# MeasOutUI.net
KiCad netlist of a schematic drawn in Altium Designer
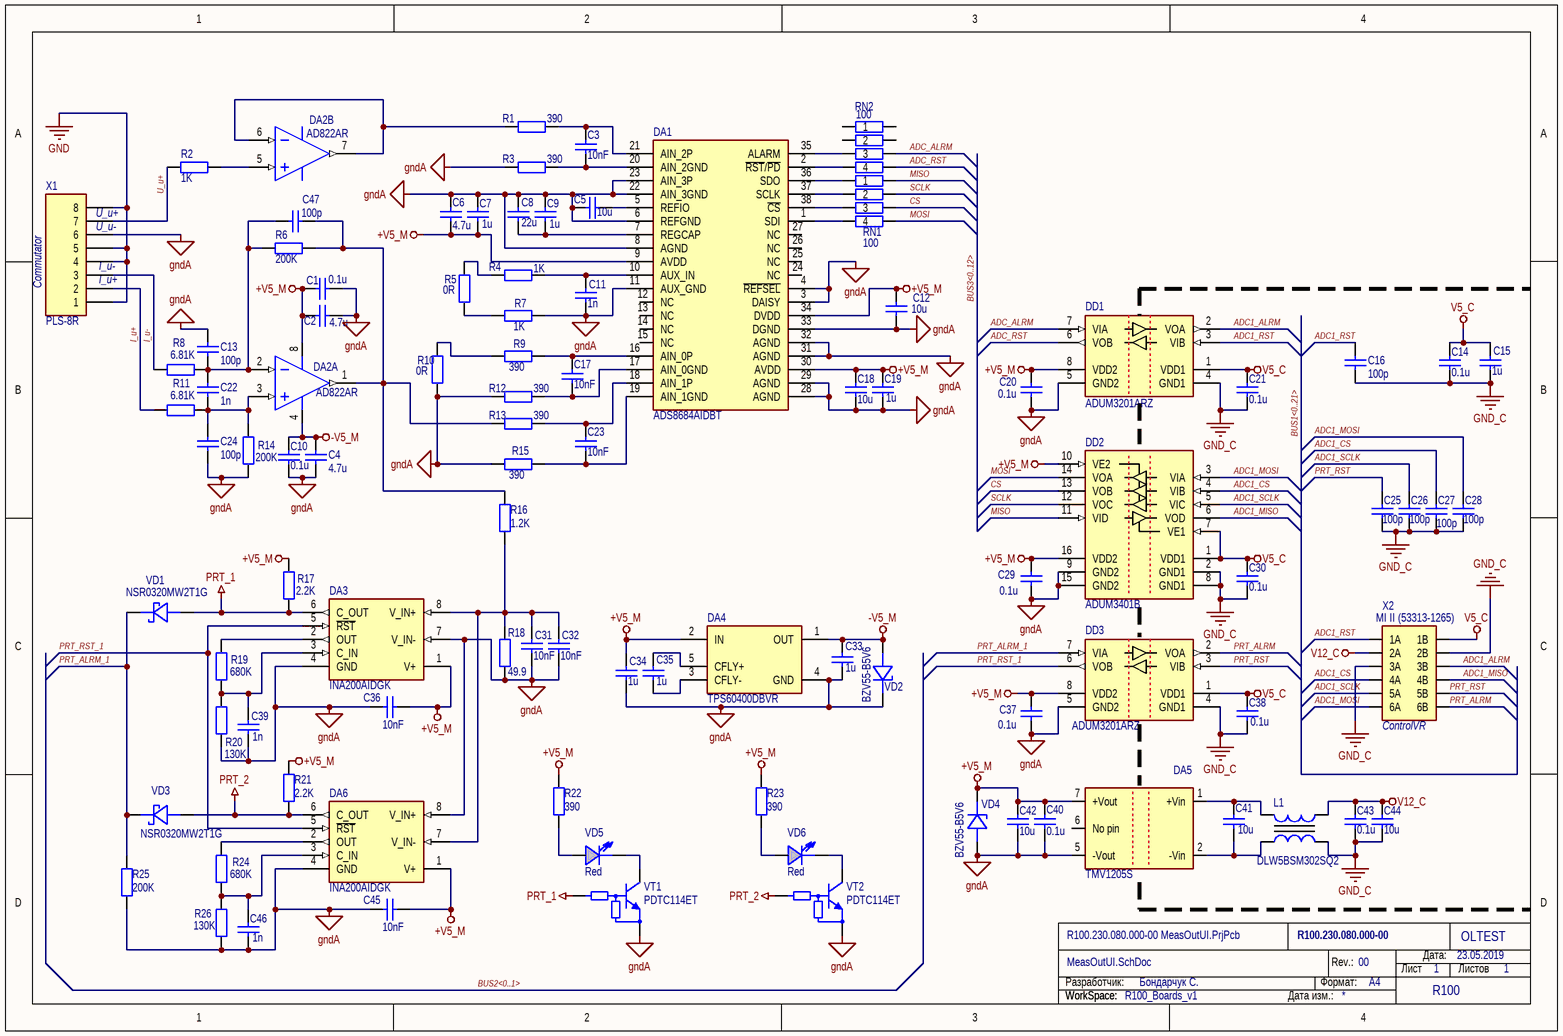
[diagram p0: MeasOutUI.SchDoc]

(export (version "E")
  (design (tool "Eeschema 10.0.6"))
  (components
    (comp (ref "C1")
      (value "0.1u")
      (footprint "mainLib:SMD_C_0603")
      (description "SMD C 0603 MURATA 50V 10% X7R")
      (fields (field (name "PARTNUMBER") "GRM188R71H104K") (field (name "MANUFACTURER") "MURATA"))
      (libsource (lib "mainRCLib") (part "C0603 0.1u 50V 10%"))
    )
    (comp (ref "C2")
      (value "4.7u")
      (footprint "mainLib:SMD_C_0805")
      (description "SMD C 0805 MURATA 50V 5% NP0")
      (fields (field (name "PARTNUMBER") "GRM21BR61E475M") (field (name "MANUFACTURER") "MURATA"))
      (libsource (lib "mainRCLib") (part "C0805 4.7u 25V 20%  X5R"))
    )
    (comp (ref "C3")
      (value "10nF")
      (footprint "mainLib:SMD_C_0603")
      (description "SMD C 0603 MURATA 100V 10% X7R")
      (fields (field (name "PARTNUMBER") "GRJ188R72A103KE11#") (field (name "MANUFACTURER") "MURATA"))
      (libsource (lib "mainRCLib") (part "C0603 10nF 100V 10%"))
    )
    (comp (ref "C4")
      (value "4.7u")
      (footprint "mainLib:SMD_C_0805")
      (description "SMD C 0805 MURATA 50V 5% NP0")
      (fields (field (name "PARTNUMBER") "GRM21BR61E475M") (field (name "MANUFACTURER") "MURATA"))
      (libsource (lib "mainRCLib") (part "C0805 4.7u 25V 20%  X5R"))
    )
    (comp (ref "C5")
      (value "10u")
      (footprint "mainLib:SMD_C_1206")
      (description "SMD C 1206 MURATA 25V 20% X5R")
      (fields (field (name "PARTNUMBER") "GRM31MR61E106M") (field (name "MANUFACTURER") "MURATA"))
      (libsource (lib "mainRCLib") (part "C1206 10u 25V 20%"))
    )
    (comp (ref "C6")
      (value "4.7u")
      (footprint "mainLib:SMD_C_0805")
      (description "SMD C 0805 MURATA 50V 5% NP0")
      (fields (field (name "PARTNUMBER") "GRM21BR61E475M") (field (name "MANUFACTURER") "MURATA"))
      (libsource (lib "mainRCLib") (part "C0805 4.7u 25V 20%  X5R"))
    )
    (comp (ref "C7")
      (value "1u")
      (footprint "mainLib:SMD_C_0603")
      (description "SMD C 0603 MURATA 25V 10% X7R")
      (fields (field (name "PARTNUMBER") "GRM188R71E105KA12") (field (name "MANUFACTURER") "MURATA"))
      (libsource (lib "mainRCLib") (part "C0603 1uF 25V 10%"))
    )
    (comp (ref "C8")
      (value "22u")
      (footprint "mainLib:SMD_C_1210")
      (description "SMD C 1210 MURATA 22uF 25V 10%  X7R")
      (fields (field (name "PARTNUMBER") "GRM32ER71E226K") (field (name "MANUFACTURER") "MURATA"))
      (libsource (lib "mainRCLib") (part "C1210 22u 25V 10%"))
    )
    (comp (ref "C9")
      (value "1u")
      (footprint "mainLib:SMD_C_0603")
      (description "SMD C 0603 MURATA 25V 10% X7R")
      (fields (field (name "PARTNUMBER") "GRM188R71E105KA12") (field (name "MANUFACTURER") "MURATA"))
      (libsource (lib "mainRCLib") (part "C0603 1uF 25V 10%"))
    )
    (comp (ref "C10")
      (value "0.1u")
      (footprint "mainLib:SMD_C_0603")
      (description "SMD C 0603 MURATA 50V 10% X7R")
      (fields (field (name "PARTNUMBER") "GRM188R71H104K") (field (name "MANUFACTURER") "MURATA"))
      (libsource (lib "mainRCLib") (part "C0603 0.1u 50V 10%"))
    )
    (comp (ref "C11")
      (value "1n")
      (footprint "mainLib:SMD_C_0603")
      (description "SMD C 0603 MURATA 50V 5% NP0")
      (fields (field (name "PARTNUMBER") "GRM1885C1H102JA01") (field (name "MANUFACTURER") "MURATA"))
      (libsource (lib "mainRCLib") (part "C0603 1n 50V 5%"))
    )
    (comp (ref "C12")
      (value "10u")
      (footprint "mainLib:SMD_C_1206")
      (description "SMD C 1206 MURATA 25V 20% X5R")
      (fields (field (name "PARTNUMBER") "GRM31MR61E106M") (field (name "MANUFACTURER") "MURATA"))
      (libsource (lib "mainRCLib") (part "C1206 10u 25V 20%"))
    )
    (comp (ref "C13")
      (value "100p")
      (footprint "mainLib:SMD_C_0603")
      (description "SMD C 0603 MURATA 100V 5% NP0")
      (fields (field (name "PARTNUMBER") "GRM1885C2A101JA01") (field (name "MANUFACTURER") "MURATA"))
      (libsource (lib "mainRCLib") (part "C0603 100p 100V 5%"))
    )
    (comp (ref "C14")
      (value "0.1u")
      (footprint "mainLib:SMD_C_0603")
      (description "SMD C 0603 MURATA 50V 10% X7R")
      (fields (field (name "PARTNUMBER") "GRM188R71H104K") (field (name "MANUFACTURER") "MURATA"))
      (libsource (lib "mainRCLib") (part "C0603 0.1u 50V 10%"))
    )
    (comp (ref "C15")
      (value "1u")
      (footprint "mainLib:SMD_C_0603")
      (description "SMD C 0603 MURATA 25V 10% X7R")
      (fields (field (name "PARTNUMBER") "GRM188R71E105KA12") (field (name "MANUFACTURER") "MURATA"))
      (libsource (lib "mainRCLib") (part "C0603 1uF 25V 10%"))
    )
    (comp (ref "C16")
      (value "100p")
      (footprint "mainLib:SMD_C_0603")
      (description "SMD C 0603 MURATA 100V 5% NP0")
      (fields (field (name "PARTNUMBER") "GRM1885C2A101JA01") (field (name "MANUFACTURER") "MURATA"))
      (libsource (lib "mainRCLib") (part "C0603 100p 100V 5%"))
    )
    (comp (ref "C17")
      (value "10nF")
      (footprint "mainLib:SMD_C_0603")
      (description "SMD C 0603 MURATA 100V 10% X7R")
      (fields (field (name "PARTNUMBER") "GRJ188R72A103KE11#") (field (name "MANUFACTURER") "MURATA"))
      (libsource (lib "mainRCLib") (part "C0603 10nF 100V 10%"))
    )
    (comp (ref "C18")
      (value "10u")
      (footprint "mainLib:SMD_C_1206")
      (description "SMD C 1206 MURATA 25V 20% X5R")
      (fields (field (name "PARTNUMBER") "GRM31MR61E106M") (field (name "MANUFACTURER") "MURATA"))
      (libsource (lib "mainRCLib") (part "C1206 10u 25V 20%"))
    )
    (comp (ref "C19")
      (value "1u")
      (footprint "mainLib:SMD_C_0603")
      (description "SMD C 0603 MURATA 25V 10% X7R")
      (fields (field (name "PARTNUMBER") "GRM188R71E105KA12") (field (name "MANUFACTURER") "MURATA"))
      (libsource (lib "mainRCLib") (part "C0603 1uF 25V 10%"))
    )
    (comp (ref "C20")
      (value "0.1u")
      (footprint "mainLib:SMD_C_0603")
      (description "SMD C 0603 MURATA 50V 10% X7R")
      (fields (field (name "PARTNUMBER") "GRM188R71H104K") (field (name "MANUFACTURER") "MURATA"))
      (libsource (lib "mainRCLib") (part "C0603 0.1u 50V 10%"))
    )
    (comp (ref "C21")
      (value "0.1u")
      (footprint "mainLib:SMD_C_0603")
      (description "SMD C 0603 MURATA 50V 10% X7R")
      (fields (field (name "PARTNUMBER") "GRM188R71H104K") (field (name "MANUFACTURER") "MURATA"))
      (libsource (lib "mainRCLib") (part "C0603 0.1u 50V 10%"))
    )
    (comp (ref "C22")
      (value "1n")
      (footprint "mainLib:SMD_C_0603")
      (description "SMD C 0603 MURATA 50V 5% NP0")
      (fields (field (name "PARTNUMBER") "GRM1885C1H102JA01") (field (name "MANUFACTURER") "MURATA"))
      (libsource (lib "mainRCLib") (part "C0603 1n 50V 5%"))
    )
    (comp (ref "C23")
      (value "10nF")
      (footprint "mainLib:SMD_C_0603")
      (description "SMD C 0603 MURATA 100V 10% X7R")
      (fields (field (name "PARTNUMBER") "GRJ188R72A103KE11#") (field (name "MANUFACTURER") "MURATA"))
      (libsource (lib "mainRCLib") (part "C0603 10nF 100V 10%"))
    )
    (comp (ref "C24")
      (value "100p")
      (footprint "mainLib:SMD_C_0603")
      (description "SMD C 0603 MURATA 100V 5% NP0")
      (fields (field (name "PARTNUMBER") "GRM1885C2A101JA01") (field (name "MANUFACTURER") "MURATA"))
      (libsource (lib "mainRCLib") (part "C0603 100p 100V 5%"))
    )
    (comp (ref "C25")
      (value "100p")
      (footprint "mainLib:SMD_C_0603")
      (description "SMD C 0603 MURATA 100V 5% NP0")
      (fields (field (name "PARTNUMBER") "GRM1885C2A101JA01") (field (name "MANUFACTURER") "MURATA"))
      (libsource (lib "mainRCLib") (part "C0603 100p 100V 5%"))
    )
    (comp (ref "C26")
      (value "100p")
      (footprint "mainLib:SMD_C_0603")
      (description "SMD C 0603 MURATA 100V 5% NP0")
      (fields (field (name "PARTNUMBER") "GRM1885C2A101JA01") (field (name "MANUFACTURER") "MURATA"))
      (libsource (lib "mainRCLib") (part "C0603 100p 100V 5%"))
    )
    (comp (ref "C27")
      (value "100p")
      (footprint "mainLib:SMD_C_0603")
      (description "SMD C 0603 MURATA 100V 5% NP0")
      (fields (field (name "PARTNUMBER") "GRM1885C2A101JA01") (field (name "MANUFACTURER") "MURATA"))
      (libsource (lib "mainRCLib") (part "C0603 100p 100V 5%"))
    )
    (comp (ref "C28")
      (value "100p")
      (footprint "mainLib:SMD_C_0603")
      (description "SMD C 0603 MURATA 100V 5% NP0")
      (fields (field (name "PARTNUMBER") "GRM1885C2A101JA01") (field (name "MANUFACTURER") "MURATA"))
      (libsource (lib "mainRCLib") (part "C0603 100p 100V 5%"))
    )
    (comp (ref "C29")
      (value "0.1u")
      (footprint "mainLib:SMD_C_0603")
      (description "SMD C 0603 MURATA 50V 10% X7R")
      (fields (field (name "PARTNUMBER") "GRM188R71H104K") (field (name "MANUFACTURER") "MURATA"))
      (libsource (lib "mainRCLib") (part "C0603 0.1u 50V 10%"))
    )
    (comp (ref "C30")
      (value "0.1u")
      (footprint "mainLib:SMD_C_0603")
      (description "SMD C 0603 MURATA 50V 10% X7R")
      (fields (field (name "PARTNUMBER") "GRM188R71H104K") (field (name "MANUFACTURER") "MURATA"))
      (libsource (lib "mainRCLib") (part "C0603 0.1u 50V 10%"))
    )
    (comp (ref "C31")
      (value "10nF")
      (footprint "mainLib:SMD_C_0805")
      (description "SMD C 0805 MURATA 100V 20% X7R")
      (fields (field (name "PARTNUMBER") "GRM216R72A103MAC4#") (field (name "MANUFACTURER") "MURATA"))
      (libsource (lib "mainRCLib") (part "C0805 10n 100V 20%"))
    )
    (comp (ref "C32")
      (value "10nF")
      (footprint "mainLib:SMD_C_0805")
      (description "SMD C 0805 MURATA 100V 20% X7R")
      (fields (field (name "PARTNUMBER") "GRM216R72A103MAC4#") (field (name "MANUFACTURER") "MURATA"))
      (libsource (lib "mainRCLib") (part "C0805 10n 100V 20%"))
    )
    (comp (ref "C33")
      (value "1u")
      (footprint "mainLib:SMD_C_0603")
      (description "SMD C 0603 MURATA 25V 10% X7R")
      (fields (field (name "PARTNUMBER") "GRM188R71E105KA12") (field (name "MANUFACTURER") "MURATA"))
      (libsource (lib "mainRCLib") (part "C0603 1uF 25V 10%"))
    )
    (comp (ref "C34")
      (value "1u")
      (footprint "mainLib:SMD_C_0603")
      (description "SMD C 0603 MURATA 25V 10% X7R")
      (fields (field (name "PARTNUMBER") "GRM188R71E105KA12") (field (name "MANUFACTURER") "MURATA"))
      (libsource (lib "mainRCLib") (part "C0603 1uF 25V 10%"))
    )
    (comp (ref "C35")
      (value "1u")
      (footprint "mainLib:SMD_C_0603")
      (description "SMD C 0603 MURATA 25V 10% X7R")
      (fields (field (name "PARTNUMBER") "GRM188R71E105KA12") (field (name "MANUFACTURER") "MURATA"))
      (libsource (lib "mainRCLib") (part "C0603 1uF 25V 10%"))
    )
    (comp (ref "C36")
      (value "10nF")
      (footprint "mainLib:SMD_C_0603")
      (description "SMD C 0603 MURATA 100V 10% X7R")
      (fields (field (name "PARTNUMBER") "GRJ188R72A103KE11#") (field (name "MANUFACTURER") "MURATA"))
      (libsource (lib "mainRCLib") (part "C0603 10nF 100V 10%"))
    )
    (comp (ref "C37")
      (value "0.1u")
      (footprint "mainLib:SMD_C_0603")
      (description "SMD C 0603 MURATA 50V 10% X7R")
      (fields (field (name "PARTNUMBER") "GRM188R71H104K") (field (name "MANUFACTURER") "MURATA"))
      (libsource (lib "mainRCLib") (part "C0603 0.1u 50V 10%"))
    )
    (comp (ref "C38")
      (value "0.1u")
      (footprint "mainLib:SMD_C_0603")
      (description "SMD C 0603 MURATA 50V 10% X7R")
      (fields (field (name "PARTNUMBER") "GRM188R71H104K") (field (name "MANUFACTURER") "MURATA"))
      (libsource (lib "mainRCLib") (part "C0603 0.1u 50V 10%"))
    )
    (comp (ref "C39")
      (value "1n")
      (footprint "mainLib:SMD_C_0603")
      (description "SMD C 0603 MURATA 50V 5% NP0")
      (fields (field (name "PARTNUMBER") "GRM1885C1H102JA01") (field (name "MANUFACTURER") "MURATA"))
      (libsource (lib "mainRCLib") (part "C0603 1n 50V 5%"))
    )
    (comp (ref "C40")
      (value "0.1u")
      (footprint "mainLib:SMD_C_0603")
      (description "SMD C 0603 MURATA 50V 10% X7R")
      (fields (field (name "PARTNUMBER") "GRM188R71H104K") (field (name "MANUFACTURER") "MURATA"))
      (libsource (lib "mainRCLib") (part "C0603 0.1u 50V 10%"))
    )
    (comp (ref "C41")
      (value "10u")
      (footprint "mainLib:SMD_C_1206")
      (description "SMD C 1206 MURATA 25V 20% X5R")
      (fields (field (name "PARTNUMBER") "GRM31MR61E106M") (field (name "MANUFACTURER") "MURATA"))
      (libsource (lib "mainRCLib") (part "C1206 10u 25V 20%"))
    )
    (comp (ref "C42")
      (value "10u")
      (footprint "mainLib:SMD_C_1206")
      (description "SMD C 1206 MURATA 25V 20% X5R")
      (fields (field (name "PARTNUMBER") "GRM31MR61E106M") (field (name "MANUFACTURER") "MURATA"))
      (libsource (lib "mainRCLib") (part "C1206 10u 25V 20%"))
    )
    (comp (ref "C43")
      (value "0.1u")
      (footprint "mainLib:SMD_C_0603")
      (description "SMD C 0603 MURATA 50V 10% X7R")
      (fields (field (name "PARTNUMBER") "GRM188R71H104K") (field (name "MANUFACTURER") "MURATA"))
      (libsource (lib "mainRCLib") (part "C0603 0.1u 50V 10%"))
    )
    (comp (ref "C44")
      (value "10u")
      (footprint "mainLib:SMD_C_1206")
      (description "SMD C 1206 MURATA 25V 20% X5R")
      (fields (field (name "PARTNUMBER") "GRM31MR61E106M") (field (name "MANUFACTURER") "MURATA"))
      (libsource (lib "mainRCLib") (part "C1206 10u 25V 20%"))
    )
    (comp (ref "C45")
      (value "10nF")
      (footprint "mainLib:SMD_C_0603")
      (description "SMD C 0603 MURATA 100V 10% X7R")
      (fields (field (name "PARTNUMBER") "GRJ188R72A103KE11#") (field (name "MANUFACTURER") "MURATA"))
      (libsource (lib "mainRCLib") (part "C0603 10nF 100V 10%"))
    )
    (comp (ref "C46")
      (value "1n")
      (footprint "mainLib:SMD_C_0603")
      (description "SMD C 0603 MURATA 50V 5% NP0")
      (fields (field (name "PARTNUMBER") "GRM1885C1H102JA01") (field (name "MANUFACTURER") "MURATA"))
      (libsource (lib "mainRCLib") (part "C0603 1n 50V 5%"))
    )
    (comp (ref "C47")
      (value "100p")
      (footprint "mainLib:SMD_C_0603")
      (description "SMD C 0603 MURATA 100V 5% NP0")
      (fields (field (name "PARTNUMBER") "GRM1885C2A101JA01") (field (name "MANUFACTURER") "MURATA"))
      (libsource (lib "mainRCLib") (part "C0603 100p 100V 5%"))
    )
    (comp (ref "DA1")
      (value "ADS8684AIDBT")
      (footprint "mainLib:TSSOP38")
      (description "16-bit 500ksps ADC with MUX")
      (fields (field (name "MANUFACTURER") "Texas Instruments"))
      (libsource (lib "mainLib") (part "ADS8684AIDBT"))
    )
    (comp (ref "DA2")
      (value "AD822AR")
      (footprint "mainLib:SOIC-8")
      (description "2xOp Ampl Rail FET 30V")
      (fields (field (name "MANUFACTURER") "Analog Devices"))
      (libsource (lib "mainLib") (part "AD822AR"))
    )
    (comp (ref "DA3")
      (value "INA200AIDGK")
      (footprint "mainLib:TSOP-8 65P490X110")
      (description "Current-Shunt Monitor Ref G=20")
      (fields (field (name "MANUFACTURER") "Texas Instruments"))
      (libsource (lib "mainLib") (part "INA200AIDGK"))
    )
    (comp (ref "DA4")
      (value "TPS60400DBVR")
      (footprint "mainLib:TI-DBV5_M")
      (fields (field (name "MANUFACTURER") "Texas Instruments"))
      (libsource (lib "mainLib") (part "TPS60400DBVR"))
    )
    (comp (ref "DA5")
      (value "TMV1205S")
      (footprint "mainLib:SIP7")
      (description "DC/DC")
      (fields (field (name "MANUFACTURER") "TRACO POWER"))
      (libsource (lib "mainLib") (part "TMV1205S"))
    )
    (comp (ref "DA6")
      (value "INA200AIDGK")
      (footprint "mainLib:TSOP-8 65P490X110")
      (description "Current-Shunt Monitor Ref G=20")
      (fields (field (name "MANUFACTURER") "Texas Instruments"))
      (libsource (lib "mainLib") (part "INA200AIDGK"))
    )
    (comp (ref "DD1")
      (value "ADUM3201ARZ")
      (footprint "mainLib:SOIC-8")
      (fields (field (name "MANUFACTURER") "Analog Devices"))
      (libsource (lib "mainLib") (part "ADUM3201ARZ"))
    )
    (comp (ref "DD2")
      (value "ADUM3401B")
      (footprint "mainLib:ADI-RW-16_N")
      (fields (field (name "MANUFACTURER") "Analog Devices") (field (name "PARTNUMBER") "ADUM3401BRWZ"))
      (libsource (lib "mainLib") (part "ADUM3401BRWZ"))
    )
    (comp (ref "DD3")
      (value "ADUM3201ARZ")
      (footprint "mainLib:SOIC-8")
      (fields (field (name "MANUFACTURER") "Analog Devices"))
      (libsource (lib "mainLib") (part "ADUM3201ARZ"))
    )
    (comp (ref "L1")
      (value "DLW5BSM302SQ2")
      (footprint "mainLib:DLW5BS(AH)")
      (description "SMD Common Mode Choke Coil 0.5A Z = 3000 Ohm / 100 MHz")
      (fields (field (name "MANUFACTURER") "MURATA"))
      (libsource (lib "mainLib") (part "DLW5BSM302SQ2"))
    )
    (comp (ref "R1")
      (value "390")
      (footprint "mainLib:SMD_R_0805")
      (description "SMD R 0805 VISHAY 0.125W 150V 1% 100ppm")
      (fields (field (name "PARTNUMBER") "CRCW0805390RFK") (field (name "MANUFACTURER") "VISHAY"))
      (libsource (lib "") (part "R0805 390R +-1%_1"))
    )
    (comp (ref "R2")
      (value "1K")
      (footprint "mainLib:SMD_R_0805")
      (description "SMD R 0805 VISHAY 0.125W 150V 1% 100ppm")
      (fields (field (name "PARTNUMBER") "CRCW08051K00FK") (field (name "MANUFACTURER") "VISHAY"))
      (libsource (lib "mainRCLib") (part "R0805 1K 1%"))
    )
    (comp (ref "R3")
      (value "390")
      (footprint "mainLib:SMD_R_0805")
      (description "SMD R 0805 VISHAY 0.125W 150V 1% 100ppm")
      (fields (field (name "PARTNUMBER") "CRCW0805390RFK") (field (name "MANUFACTURER") "VISHAY"))
      (libsource (lib "") (part "R0805 390R +-1%_1"))
    )
    (comp (ref "R4")
      (value "1K")
      (footprint "mainLib:SMD_R_0603")
      (description "SMD R 0603 VISHAY 0.1W 75V 1% 100ppm")
      (fields (field (name "PARTNUMBER") "CRCW06031K00FK") (field (name "MANUFACTURER") "VISHAY"))
      (libsource (lib "mainRCLib") (part "R0603 1K 1%"))
    )
    (comp (ref "R5")
      (value "0R")
      (footprint "mainLib:SMD_R_0603")
      (description "SMD R 0603 VISHAY 0.1W 75V 1% 100ppm")
      (fields (field (name "PARTNUMBER") "CRCW06030000Z0") (field (name "MANUFACTURER") "VISHAY"))
      (libsource (lib "mainRCLib") (part "R0603 0R 1%"))
    )
    (comp (ref "R6")
      (value "200K")
      (footprint "mainLib:SMD_R_0805")
      (description "SMD R 0805 VISHAY 0.125W 150V 1% 100ppm")
      (fields (field (name "PARTNUMBER") "CRCW0805200KFK") (field (name "MANUFACTURER") "VISHAY"))
      (libsource (lib "mainRCLib") (part "R0805 200K 1%"))
    )
    (comp (ref "R7")
      (value "1K")
      (footprint "mainLib:SMD_R_0603")
      (description "SMD R 0603 VISHAY 0.1W 75V 1% 100ppm")
      (fields (field (name "PARTNUMBER") "CRCW06031K00FK") (field (name "MANUFACTURER") "VISHAY"))
      (libsource (lib "mainRCLib") (part "R0603 1K 1%"))
    )
    (comp (ref "R8")
      (value "6.81K")
      (footprint "mainLib:SMD_R_1206")
      (description "SMD R 1206 VISHAY 0.25W 150V 1% 100ppm")
      (fields (field (name "PARTNUMBER") "CRCW12066K81FK") (field (name "MANUFACTURER") "VISHAY"))
      (libsource (lib "mainRCLib") (part "R1206 6.81K 1%"))
    )
    (comp (ref "R9")
      (value "390")
      (footprint "mainLib:SMD_R_0805")
      (description "SMD R 0805 VISHAY 0.125W 150V 1% 100ppm")
      (fields (field (name "PARTNUMBER") "CRCW0805390RFK") (field (name "MANUFACTURER") "VISHAY"))
      (libsource (lib "") (part "R0805 390R +-1%_1"))
    )
    (comp (ref "R10")
      (value "0R")
      (footprint "mainLib:SMD_R_0603")
      (description "SMD R 0603 VISHAY 0.1W 75V 1% 100ppm")
      (fields (field (name "PARTNUMBER") "CRCW06030000Z0") (field (name "MANUFACTURER") "VISHAY"))
      (libsource (lib "mainRCLib") (part "R0603 0R 1%"))
    )
    (comp (ref "R11")
      (value "6.81K")
      (footprint "mainLib:SMD_R_1206")
      (description "SMD R 1206 VISHAY 0.25W 150V 1% 100ppm")
      (fields (field (name "PARTNUMBER") "CRCW12066K81FK") (field (name "MANUFACTURER") "VISHAY"))
      (libsource (lib "mainRCLib") (part "R1206 6.81K 1%"))
    )
    (comp (ref "R12")
      (value "390")
      (footprint "mainLib:SMD_R_0805")
      (description "SMD R 0805 VISHAY 0.125W 150V 1% 100ppm")
      (fields (field (name "PARTNUMBER") "CRCW0805390RFK") (field (name "MANUFACTURER") "VISHAY"))
      (libsource (lib "") (part "R0805 390R +-1%_1"))
    )
    (comp (ref "R13")
      (value "390")
      (footprint "mainLib:SMD_R_0805")
      (description "SMD R 0805 VISHAY 0.125W 150V 1% 100ppm")
      (fields (field (name "PARTNUMBER") "CRCW0805390RFK") (field (name "MANUFACTURER") "VISHAY"))
      (libsource (lib "") (part "R0805 390R +-1%_1"))
    )
    (comp (ref "R14")
      (value "200K")
      (footprint "mainLib:SMD_R_0805")
      (description "SMD R 0805 VISHAY 0.125W 150V 1% 100ppm")
      (fields (field (name "PARTNUMBER") "CRCW0805200KFK") (field (name "MANUFACTURER") "VISHAY"))
      (libsource (lib "") (part "R0805 200K 1%_1"))
    )
    (comp (ref "R15")
      (value "390")
      (footprint "mainLib:SMD_R_0805")
      (description "SMD R 0805 VISHAY 0.125W 150V 1% 100ppm")
      (fields (field (name "PARTNUMBER") "CRCW0805390RFK") (field (name "MANUFACTURER") "VISHAY"))
      (libsource (lib "") (part "R0805 390R +-1%_1"))
    )
    (comp (ref "R16")
      (value "1.2K")
      (footprint "mainLib:SMD_R_0805")
      (description "SMD R 0805 VISHAY 0.125W 150V 1% 100ppm")
      (fields (field (name "PARTNUMBER") "CRCW08051K2FK") (field (name "MANUFACTURER") "VISHAY"))
      (libsource (lib "mainRCLib") (part "R0805 1.2K 1%"))
    )
    (comp (ref "R17")
      (value "2.2K")
      (footprint "mainLib:SMD_R_0805")
      (description "SMD R 0805 VISHAY 0.125W 150V 1% 100ppm")
      (fields (field (name "PARTNUMBER") "CRCW08052K20FK") (field (name "MANUFACTURER") "VISHAY"))
      (libsource (lib "mainRCLib") (part "R0805 2.2K 1%"))
    )
    (comp (ref "R18")
      (value "49.9")
      (footprint "mainLib:SMD_R_0805")
      (description "SMD R 0805 VISHAY 0.125W 150V 1% 100ppm")
      (fields (field (name "PARTNUMBER") "CRCW080549R9FK") (field (name "MANUFACTURER") "VISHAY"))
      (libsource (lib "mainRCLib") (part "R0805 49.9 1%"))
    )
    (comp (ref "R19")
      (value "680K")
      (footprint "mainLib:SMD_R_0805")
      (description "SMD R 0805 VISHAY 0.125W 150V 1% 100ppm")
      (fields (field (name "PARTNUMBER") "CRCW0805680KFK") (field (name "MANUFACTURER") "VISHAY"))
      (libsource (lib "") (part "R0805 680K 1%_1"))
    )
    (comp (ref "R20")
      (value "130K")
      (footprint "mainLib:SMD_R_0805")
      (description "SMD R 0805 VISHAY 0.125W 150V 1% 100ppm")
      (fields (field (name "PARTNUMBER") "CRCW0805130KFK") (field (name "MANUFACTURER") "VISHAY"))
      (libsource (lib "mainRCLib") (part "R0805 130K 1%"))
    )
    (comp (ref "R21")
      (value "2.2K")
      (footprint "mainLib:SMD_R_0805")
      (description "SMD R 0805 VISHAY 0.125W 150V 1% 100ppm")
      (fields (field (name "PARTNUMBER") "CRCW08052K20FK") (field (name "MANUFACTURER") "VISHAY"))
      (libsource (lib "mainRCLib") (part "R0805 2.2K 1%"))
    )
    (comp (ref "R22")
      (value "390")
      (footprint "mainLib:SMD_R_0805")
      (description "SMD R 0805 VISHAY 0.125W 150V 1% 100ppm")
      (fields (field (name "PARTNUMBER") "CRCW0805390RFK") (field (name "MANUFACTURER") "VISHAY"))
      (libsource (lib "mainRCLib") (part "R0805 390R +-1%"))
    )
    (comp (ref "R23")
      (value "390")
      (footprint "mainLib:SMD_R_0805")
      (description "SMD R 0805 VISHAY 0.125W 150V 1% 100ppm")
      (fields (field (name "PARTNUMBER") "CRCW0805390RFK") (field (name "MANUFACTURER") "VISHAY"))
      (libsource (lib "mainRCLib") (part "R0805 390R +-1%"))
    )
    (comp (ref "R24")
      (value "680K")
      (footprint "mainLib:SMD_R_0805")
      (description "SMD R 0805 VISHAY 0.125W 150V 1% 100ppm")
      (fields (field (name "PARTNUMBER") "CRCW0805680KFK") (field (name "MANUFACTURER") "VISHAY"))
      (libsource (lib "mainRCLib") (part "R0805 680K 1%"))
    )
    (comp (ref "R25")
      (value "200K")
      (footprint "mainLib:SMD_R_0805")
      (description "SMD R 0805 VISHAY 0.125W 150V 1% 100ppm")
      (fields (field (name "PARTNUMBER") "CRCW0805200KFK") (field (name "MANUFACTURER") "VISHAY"))
      (libsource (lib "") (part "R0805 200K 1%_1"))
    )
    (comp (ref "R26")
      (value "130K")
      (footprint "mainLib:SMD_R_0805")
      (description "SMD R 0805 VISHAY 0.125W 150V 1% 100ppm")
      (fields (field (name "PARTNUMBER") "CRCW0805130KFK") (field (name "MANUFACTURER") "VISHAY"))
      (libsource (lib "mainRCLib") (part "R0805 130K 1%"))
    )
    (comp (ref "RN1")
      (value "100")
      (footprint "mainLib:CRA06S")
      (description "SMD RESISTOR ARRAY VISHAY 0.063W 50V 1% 100ppm")
      (fields (field (name "PARTNUMBER") "CRA06S083100RF") (field (name "MANUFACTURER") "VISHAY"))
      (libsource (lib "mainRCLib") (part "CRA06S 4x100 1%"))
    )
    (comp (ref "RN2")
      (value "100")
      (footprint "mainLib:CRA06S")
      (description "SMD RESISTOR ARRAY VISHAY 0.063W 50V 1% 100ppm")
      (fields (field (name "PARTNUMBER") "CRA06S083100RF") (field (name "MANUFACTURER") "VISHAY"))
      (libsource (lib "mainRCLib") (part "CRA06S 4x100 1%"))
    )
    (comp (ref "VD1")
      (value "NSR0320MW2T1G")
      (footprint "mainLib:SOD 2 FL250X100")
      (description "Vr=20V If=1A Schottky Diode")
      (fields (field (name "MANUFACTURER") "ON SEMICONDUCTOR"))
      (libsource (lib "mainLib") (part "NSR0320MW2T1G"))
    )
    (comp (ref "VD2")
      (value "BZV55-B5V6")
      (footprint "mainLib:SOD80C")
      (description "0.5W Vz=5.6V +-2%")
      (fields (field (name "MANUFACTURER") "NXP"))
      (libsource (lib "mainLib") (part "BZV55-B5V6"))
    )
    (comp (ref "VD3")
      (value "NSR0320MW2T1G")
      (footprint "mainLib:SOD 2 FL250X100")
      (description "Vr=20V If=1A Schottky Diode")
      (fields (field (name "MANUFACTURER") "ON SEMICONDUCTOR"))
      (libsource (lib "mainLib") (part "NSR0320MW2T1G"))
    )
    (comp (ref "VD4")
      (value "BZV55-B5V6")
      (footprint "mainLib:SOD80C")
      (description "0.5W Vz=5.6V +-2%")
      (fields (field (name "MANUFACTURER") "NXP"))
      (libsource (lib "mainLib") (part "BZV55-B5V6"))
    )
    (comp (ref "VD5")
      (value "Red")
      (footprint "mainLib:SMD_LED_LL_Red")
      (description "LED Red SMD")
      (fields (field (name "PARTNUMBER") "LL-S172SC-2S") (field (name "MANUFACTURER") "Lucky Light"))
      (libsource (lib "mainLib") (part "LL-S172SC-2S"))
    )
    (comp (ref "VD6")
      (value "Red")
      (footprint "mainLib:SMD_LED_LL_Red")
      (description "LED Red SMD")
      (fields (field (name "PARTNUMBER") "LL-S172SC-2S") (field (name "MANUFACTURER") "Lucky Light"))
      (libsource (lib "mainLib") (part "LL-S172SC-2S"))
    )
    (comp (ref "VT1")
      (value "PDTC114ET")
      (footprint "mainLib:SOT23-3")
      (description "Digital Transistor (BRT), R1=10 kOhm, R2=10 kOhm, NPN Transistor")
      (fields (field (name "MANUFACTURER") "On Semiconductor"))
      (libsource (lib "mainLib") (part "PDTC114ET"))
    )
    (comp (ref "VT2")
      (value "PDTC114ET")
      (footprint "mainLib:SOT23-3")
      (description "Digital Transistor (BRT), R1=10 kOhm, R2=10 kOhm, NPN Transistor")
      (fields (field (name "MANUFACTURER") "On Semiconductor"))
      (libsource (lib "mainLib") (part "PDTC114ET"))
    )
    (comp (ref "X1")
      (value "PLS-8R")
      (footprint "mainLib:PLS_R-1x8 (22-28-9080 mplex)")
      (description "Molex KK254 42377 LS=2.54 4A 250VDC PCB")
      (fields (field (name "PARTNUMBER") "22-28-9080") (field (name "MANUFACTURER") "MOLEX"))
      (libsource (lib "mainLib") (part "PLS-8R (22-28-9080)"))
    )
    (comp (ref "X2")
      (value "MI II (53313-1265)")
      (footprint "mainLib:53313-1265")
      (description "MI II 12 (6x2row), 2A 125V 2mm")
      (fields (field (name "PARTNUMBER") "53313-1265") (field (name "MANUFACTURER") "MOLEX"))
      (libsource (lib "mainLib") (part "53313-1265"))
    )
  )
  (nets
    (net (code "4") (name "+V5_M") (class "Default")
      (node (ref "C1") (pin "2") (pinfunction "2_2") (pintype "passive"))
      (node (ref "C12") (pin "2") (pinfunction "2_2") (pintype "passive"))
      (node (ref "C18") (pin "2") (pinfunction "2_2") (pintype "passive"))
      (node (ref "C19") (pin "2") (pinfunction "2_2") (pintype "passive"))
      (node (ref "C2") (pin "1") (pinfunction "1_1") (pintype "passive"))
      (node (ref "C20") (pin "2") (pinfunction "2_2") (pintype "passive"))
      (node (ref "C29") (pin "2") (pinfunction "2_2") (pintype "passive"))
      (node (ref "C34") (pin "2") (pinfunction "2_2") (pintype "passive"))
      (node (ref "C36") (pin "2") (pinfunction "2_2") (pintype "passive"))
      (node (ref "C37") (pin "2") (pinfunction "2_2") (pintype "passive"))
      (node (ref "C40") (pin "2") (pinfunction "2_2") (pintype "passive"))
      (node (ref "C42") (pin "2") (pinfunction "2_2") (pintype "passive"))
      (node (ref "C45") (pin "2") (pinfunction "2_2") (pintype "passive"))
      (node (ref "C6") (pin "1") (pinfunction "1_1") (pintype "passive"))
      (node (ref "C7") (pin "1") (pinfunction "1_1") (pintype "passive"))
      (node (ref "DA1") (pin "30") (pinfunction "AVDD_30") (pintype "passive"))
      (node (ref "DA1") (pin "34") (pinfunction "DVDD_34") (pintype "passive"))
      (node (ref "DA1") (pin "9") (pinfunction "AVDD_9") (pintype "passive"))
      (node (ref "DA2") (pin "8") (pinfunction "V+_8") (pintype "power_in"))
      (node (ref "DA3") (pin "1") (pinfunction "V+_1") (pintype "power_in"))
      (node (ref "DA4") (pin "2") (pinfunction "IN_2") (pintype "power_in"))
      (node (ref "DA5") (pin "7") (pinfunction "+Vout_7") (pintype "passive"))
      (node (ref "DA6") (pin "1") (pinfunction "V+_1") (pintype "power_in"))
      (node (ref "DD1") (pin "8") (pinfunction "VDD2_8") (pintype "power_in"))
      (node (ref "DD2") (pin "10") (pinfunction "VE2_10") (pintype "input"))
      (node (ref "DD2") (pin "16") (pinfunction "VDD2_16") (pintype "power_in"))
      (node (ref "DD3") (pin "8") (pinfunction "VDD2_8") (pintype "power_in"))
      (node (ref "R17") (pin "2") (pinfunction "2_2") (pintype "passive"))
      (node (ref "R21") (pin "2") (pinfunction "2_2") (pintype "passive"))
      (node (ref "R22") (pin "2") (pinfunction "2_2") (pintype "passive"))
      (node (ref "R23") (pin "2") (pinfunction "2_2") (pintype "passive"))
      (node (ref "VD4") (pin "2") (pinfunction "CATHODE_2") (pintype "passive"))
    )
    (net (code "5") (name "-V5_M") (class "Default")
      (node (ref "C10") (pin "1") (pinfunction "1_1") (pintype "passive"))
      (node (ref "C33") (pin "2") (pinfunction "2_2") (pintype "passive"))
      (node (ref "C4") (pin "2") (pinfunction "2_2") (pintype "passive"))
      (node (ref "DA2") (pin "4") (pinfunction "V-_4") (pintype "power_in"))
      (node (ref "DA4") (pin "1") (pinfunction "OUT_1") (pintype "power_in"))
      (node (ref "VD2") (pin "1") (pinfunction "ANODE_1") (pintype "passive"))
    )
    (net (code "6") (name "/ADC1_ALRM") (class "Default")
      (node (ref "DD1") (pin "2") (pinfunction "VOA_2") (pintype "output"))
      (node (ref "X2") (pin "3B") (pinfunction "3B_3B") (pintype "passive"))
    )
    (net (code "7") (name "/ADC1_CS") (class "Default")
      (node (ref "C27") (pin "2") (pinfunction "2_2") (pintype "passive"))
      (node (ref "DD2") (pin "4") (pinfunction "VIB_4") (pintype "input"))
      (node (ref "X2") (pin "4A") (pinfunction "4A_4A") (pintype "passive"))
    )
    (net (code "8") (name "/ADC1_MISO") (class "Default")
      (node (ref "DD2") (pin "6") (pinfunction "VOD_6") (pintype "tri_state"))
      (node (ref "X2") (pin "4B") (pinfunction "4B_4B") (pintype "passive"))
    )
    (net (code "9") (name "/ADC1_MOSI") (class "Default")
      (node (ref "C28") (pin "2") (pinfunction "2_2") (pintype "passive"))
      (node (ref "DD2") (pin "3") (pinfunction "VIA_3") (pintype "input"))
      (node (ref "X2") (pin "6A") (pinfunction "6A_6A") (pintype "passive"))
    )
    (net (code "10") (name "/ADC1_RST") (class "Default")
      (node (ref "C16") (pin "2") (pinfunction "2_2") (pintype "passive"))
      (node (ref "DD1") (pin "3") (pinfunction "VIB_3") (pintype "input"))
      (node (ref "X2") (pin "1A") (pinfunction "1A_1A") (pintype "passive"))
    )
    (net (code "11") (name "/ADC1_SCLK") (class "Default")
      (node (ref "C26") (pin "2") (pinfunction "2_2") (pintype "passive"))
      (node (ref "DD2") (pin "5") (pinfunction "VIC_5") (pintype "input"))
      (node (ref "X2") (pin "5A") (pinfunction "5A_5A") (pintype "passive"))
    )
    (net (code "12") (name "/ADC_ALRM") (class "Default")
      (node (ref "DD1") (pin "7") (pinfunction "VIA_7") (pintype "input"))
      (node (ref "RN2") (pin "6") (pinfunction "6_6") (pintype "passive"))
    )
    (net (code "13") (name "/ADC_RST") (class "Default")
      (node (ref "DD1") (pin "6") (pinfunction "VOB_6") (pintype "output"))
      (node (ref "RN2") (pin "5") (pinfunction "5_5") (pintype "passive"))
    )
    (net (code "14") (name "/CS") (class "Default")
      (node (ref "DD2") (pin "13") (pinfunction "VOB_13") (pintype "tri_state"))
      (node (ref "RN1") (pin "6") (pinfunction "6_6") (pintype "passive"))
    )
    (net (code "15") (name "/I_u+") (class "Default")
      (node (ref "R11") (pin "1") (pinfunction "1_1") (pintype "passive"))
      (node (ref "X1") (pin "2") (pinfunction "2_2") (pintype "passive"))
    )
    (net (code "16") (name "/I_u-") (class "Default")
      (node (ref "R8") (pin "1") (pinfunction "1_1") (pintype "passive"))
      (node (ref "X1") (pin "3") (pinfunction "3_3") (pintype "passive"))
    )
    (net (code "17") (name "/MISO") (class "Default")
      (node (ref "DD2") (pin "11") (pinfunction "VID_11") (pintype "input"))
      (node (ref "RN1") (pin "8") (pinfunction "8_8") (pintype "passive"))
    )
    (net (code "18") (name "/MOSI") (class "Default")
      (node (ref "DD2") (pin "14") (pinfunction "VOA_14") (pintype "tri_state"))
      (node (ref "RN1") (pin "5") (pinfunction "5_5") (pintype "passive"))
    )
    (net (code "19") (name "/PRT_ALRM") (class "Default")
      (node (ref "DD3") (pin "2") (pinfunction "VOA_2") (pintype "output"))
      (node (ref "X2") (pin "6B") (pinfunction "6B_6B") (pintype "passive"))
    )
    (net (code "20") (name "/PRT_ALRM_1") (class "Default")
      (node (ref "DD3") (pin "7") (pinfunction "VIA_7") (pintype "input"))
      (node (ref "R25") (pin "2") (pinfunction "2_2") (pintype "passive"))
      (node (ref "VD1") (pin "1") (pinfunction "CATHODE_1") (pintype "passive"))
      (node (ref "VD3") (pin "1") (pinfunction "CATHODE_1") (pintype "passive"))
    )
    (net (code "21") (name "/PRT_RST") (class "Default")
      (node (ref "C25") (pin "2") (pinfunction "2_2") (pintype "passive"))
      (node (ref "DD3") (pin "3") (pinfunction "VIB_3") (pintype "input"))
      (node (ref "X2") (pin "5B") (pinfunction "5B_5B") (pintype "passive"))
    )
    (net (code "22") (name "/PRT_RST_1") (class "Default")
      (node (ref "DA3") (pin "5") (pinfunction "~{RST}_5") (pintype "input"))
      (node (ref "DA6") (pin "5") (pinfunction "~{RST}_5") (pintype "input"))
      (node (ref "DD3") (pin "6") (pinfunction "VOB_6") (pintype "output"))
    )
    (net (code "23") (name "/SCLK") (class "Default")
      (node (ref "DD2") (pin "12") (pinfunction "VOC_12") (pintype "tri_state"))
      (node (ref "RN1") (pin "7") (pinfunction "7_7") (pintype "passive"))
    )
    (net (code "24") (name "/U_u+") (class "Default")
      (node (ref "R2") (pin "1") (pinfunction "1_1") (pintype "passive"))
      (node (ref "X1") (pin "7") (pinfunction "7_7") (pintype "passive"))
    )
    (net (code "28") (name "GND") (class "Default")
      (node (ref "X1") (pin "1") (pinfunction "1_1") (pintype "passive"))
      (node (ref "X1") (pin "4") (pinfunction "4_4") (pintype "passive"))
      (node (ref "X1") (pin "5") (pinfunction "5_5") (pintype "passive"))
      (node (ref "X1") (pin "8") (pinfunction "8_8") (pintype "passive"))
    )
    (net (code "29") (name "GND_C") (class "Default")
      (node (ref "C14") (pin "1") (pinfunction "1_1") (pintype "passive"))
      (node (ref "C15") (pin "1") (pinfunction "1_1") (pintype "passive"))
      (node (ref "C16") (pin "1") (pinfunction "1_1") (pintype "passive"))
      (node (ref "C21") (pin "1") (pinfunction "1_1") (pintype "passive"))
      (node (ref "C25") (pin "1") (pinfunction "1_1") (pintype "passive"))
      (node (ref "C26") (pin "1") (pinfunction "1_1") (pintype "passive"))
      (node (ref "C27") (pin "1") (pinfunction "1_1") (pintype "passive"))
      (node (ref "C28") (pin "1") (pinfunction "1_1") (pintype "passive"))
      (node (ref "C30") (pin "1") (pinfunction "1_1") (pintype "passive"))
      (node (ref "C38") (pin "1") (pinfunction "1_1") (pintype "passive"))
      (node (ref "C43") (pin "1") (pinfunction "1_1") (pintype "passive"))
      (node (ref "C44") (pin "1") (pinfunction "1_1") (pintype "passive"))
      (node (ref "DD1") (pin "4") (pinfunction "GND1_4") (pintype "power_in"))
      (node (ref "DD2") (pin "2") (pinfunction "GND1_2") (pintype "power_in"))
      (node (ref "DD2") (pin "8") (pinfunction "GND1_8") (pintype "power_in"))
      (node (ref "DD3") (pin "4") (pinfunction "GND1_4") (pintype "power_in"))
      (node (ref "L1") (pin "2") (pinfunction "2_2") (pintype "passive"))
      (node (ref "X2") (pin "2B") (pinfunction "2B_2B") (pintype "passive"))
      (node (ref "X2") (pin "3A") (pinfunction "3A_3A") (pintype "passive"))
    )
    (net (code "30") (name "Net-(DA1-AIN_0GND)") (class "Default")
      (node (ref "C17") (pin "1") (pinfunction "1_1") (pintype "passive"))
      (node (ref "DA1") (pin "17") (pinfunction "AIN_0GND_17") (pintype "passive"))
      (node (ref "R12") (pin "2") (pinfunction "2_2") (pintype "passive"))
    )
    (net (code "31") (name "Net-(DA1-AIN_0P)") (class "Default")
      (node (ref "C17") (pin "2") (pinfunction "2_2") (pintype "passive"))
      (node (ref "DA1") (pin "16") (pinfunction "AIN_0P_16") (pintype "passive"))
      (node (ref "R9") (pin "2") (pinfunction "2_2") (pintype "passive"))
    )
    (net (code "32") (name "Net-(DA1-AIN_1GND)") (class "Default")
      (node (ref "C23") (pin "1") (pinfunction "1_1") (pintype "passive"))
      (node (ref "DA1") (pin "19") (pinfunction "AIN_1GND_19") (pintype "passive"))
      (node (ref "R15") (pin "2") (pinfunction "2_2") (pintype "passive"))
    )
    (net (code "33") (name "Net-(DA1-AIN_1P)") (class "Default")
      (node (ref "C23") (pin "2") (pinfunction "2_2") (pintype "passive"))
      (node (ref "DA1") (pin "18") (pinfunction "AIN_1P_18") (pintype "passive"))
      (node (ref "R13") (pin "2") (pinfunction "2_2") (pintype "passive"))
    )
    (net (code "34") (name "Net-(DA1-AIN_2GND)") (class "Default")
      (node (ref "C3") (pin "1") (pinfunction "1_1") (pintype "passive"))
      (node (ref "DA1") (pin "20") (pinfunction "AIN_2GND_20") (pintype "passive"))
      (node (ref "R3") (pin "2") (pinfunction "2_2") (pintype "passive"))
    )
    (net (code "35") (name "Net-(DA1-AIN_2P)") (class "Default")
      (node (ref "C3") (pin "2") (pinfunction "2_2") (pintype "passive"))
      (node (ref "DA1") (pin "21") (pinfunction "AIN_2P_21") (pintype "passive"))
      (node (ref "R1") (pin "2") (pinfunction "2_2") (pintype "passive"))
    )
    (net (code "36") (name "Net-(DA1-ALARM)") (class "Default")
      (node (ref "DA1") (pin "35") (pinfunction "ALARM_35") (pintype "passive"))
      (node (ref "RN2") (pin "3") (pinfunction "3_3") (pintype "passive"))
    )
    (net (code "37") (name "Net-(DA1-AUX_IN)") (class "Default")
      (node (ref "C11") (pin "2") (pinfunction "2_2") (pintype "passive"))
      (node (ref "DA1") (pin "10") (pinfunction "AUX_IN_10") (pintype "power_in"))
      (node (ref "R4") (pin "2") (pinfunction "2_2") (pintype "passive"))
    )
    (net (code "38") (name "Net-(DA1-REFIO)") (class "Default")
      (node (ref "C5") (pin "1") (pinfunction "1_1") (pintype "passive"))
      (node (ref "DA1") (pin "5") (pinfunction "REFIO_5") (pintype "power_in"))
    )
    (net (code "39") (name "Net-(DA1-REGCAP)") (class "Default")
      (node (ref "C8") (pin "1") (pinfunction "1_1") (pintype "passive"))
      (node (ref "C9") (pin "1") (pinfunction "1_1") (pintype "passive"))
      (node (ref "DA1") (pin "7") (pinfunction "REGCAP_7") (pintype "power_in"))
    )
    (net (code "40") (name "Net-(DA1-SCLK)") (class "Default")
      (node (ref "DA1") (pin "37") (pinfunction "SCLK_37") (pintype "passive"))
      (node (ref "RN1") (pin "2") (pinfunction "2_2") (pintype "passive"))
    )
    (net (code "41") (name "Net-(DA1-SDI)") (class "Default")
      (node (ref "DA1") (pin "1") (pinfunction "SDI_1") (pintype "passive"))
      (node (ref "RN1") (pin "4") (pinfunction "4_4") (pintype "passive"))
    )
    (net (code "42") (name "Net-(DA1-SDO)") (class "Default")
      (node (ref "DA1") (pin "36") (pinfunction "SDO_36") (pintype "passive"))
      (node (ref "RN1") (pin "1") (pinfunction "1_1") (pintype "passive"))
    )
    (net (code "43") (name "Net-(DA1-~{CS})") (class "Default")
      (node (ref "DA1") (pin "38") (pinfunction "~{CS}_38") (pintype "passive"))
      (node (ref "RN1") (pin "3") (pinfunction "3_3") (pintype "passive"))
    )
    (net (code "44") (name "Net-(DA1-~{RST}{slash}~{PD})") (class "Default")
      (node (ref "DA1") (pin "2") (pinfunction "~{RST}/~{PD}_2") (pintype "power_in"))
      (node (ref "RN2") (pin "4") (pinfunction "4_4") (pintype "passive"))
    )
    (net (code "45") (name "Net-(DA2A-IN_A+)") (class "Default")
      (node (ref "C22") (pin "1") (pinfunction "1_1") (pintype "passive"))
      (node (ref "C24") (pin "1") (pinfunction "1_1") (pintype "passive"))
      (node (ref "DA2") (pin "3") (pinfunction "IN_A+_3") (pintype "input"))
      (node (ref "R11") (pin "2") (pinfunction "2_2") (pintype "passive"))
      (node (ref "R14") (pin "2") (pinfunction "2_2") (pintype "passive"))
    )
    (net (code "46") (name "Net-(DA2A-IN_A-)") (class "Default")
      (node (ref "C13") (pin "2") (pinfunction "2_2") (pintype "passive"))
      (node (ref "C22") (pin "2") (pinfunction "2_2") (pintype "passive"))
      (node (ref "C47") (pin "1") (pinfunction "1_1") (pintype "passive"))
      (node (ref "DA2") (pin "2") (pinfunction "IN_A-_2") (pintype "input"))
      (node (ref "R6") (pin "1") (pinfunction "1_1") (pintype "passive"))
      (node (ref "R8") (pin "2") (pinfunction "2_2") (pintype "passive"))
    )
    (net (code "47") (name "Net-(DA2A-OUT_A)") (class "Default")
      (node (ref "C47") (pin "2") (pinfunction "2_2") (pintype "passive"))
      (node (ref "DA2") (pin "1") (pinfunction "OUT_A_1") (pintype "output"))
      (node (ref "R13") (pin "1") (pinfunction "1_1") (pintype "passive"))
      (node (ref "R16") (pin "2") (pinfunction "2_2") (pintype "passive"))
      (node (ref "R6") (pin "2") (pinfunction "2_2") (pintype "passive"))
    )
    (net (code "48") (name "Net-(DA2B-IN_B+)") (class "Default")
      (node (ref "DA2") (pin "5") (pinfunction "IN_B+_5") (pintype "input"))
      (node (ref "R2") (pin "2") (pinfunction "2_2") (pintype "passive"))
    )
    (net (code "49") (name "Net-(DA2B-IN_B-)") (class "Default")
      (node (ref "DA2") (pin "6") (pinfunction "IN_B-_6") (pintype "input"))
      (node (ref "DA2") (pin "7") (pinfunction "OUT_B_7") (pintype "output"))
      (node (ref "R1") (pin "1") (pinfunction "1_1") (pintype "passive"))
    )
    (net (code "50") (name "Net-(DA3-C_IN)") (class "Default")
      (node (ref "C39") (pin "2") (pinfunction "2_2") (pintype "passive"))
      (node (ref "DA3") (pin "3") (pinfunction "C_IN_3") (pintype "input"))
      (node (ref "R19") (pin "1") (pinfunction "1_1") (pintype "passive"))
      (node (ref "R20") (pin "2") (pinfunction "2_2") (pintype "passive"))
    )
    (net (code "51") (name "Net-(DA3-OUT)") (class "Default")
      (node (ref "DA3") (pin "2") (pinfunction "OUT_2") (pintype "output"))
      (node (ref "R19") (pin "2") (pinfunction "2_2") (pintype "passive"))
    )
    (net (code "52") (name "Net-(DA3-V_IN+)") (class "Default")
      (node (ref "C31") (pin "2") (pinfunction "2_2") (pintype "passive"))
      (node (ref "C32") (pin "2") (pinfunction "2_2") (pintype "passive"))
      (node (ref "DA3") (pin "8") (pinfunction "V_IN+_8") (pintype "input"))
      (node (ref "DA6") (pin "7") (pinfunction "V_IN-_7") (pintype "input"))
      (node (ref "R16") (pin "1") (pinfunction "1_1") (pintype "passive"))
      (node (ref "R18") (pin "2") (pinfunction "2_2") (pintype "passive"))
    )
    (net (code "53") (name "Net-(DA4-CFLY+)") (class "Default")
      (node (ref "C35") (pin "2") (pinfunction "2_2") (pintype "passive"))
      (node (ref "DA4") (pin "5") (pinfunction "CFLY+_5") (pintype "passive"))
    )
    (net (code "54") (name "Net-(DA4-CFLY-)") (class "Default")
      (node (ref "C35") (pin "1") (pinfunction "1_1") (pintype "passive"))
      (node (ref "DA4") (pin "3") (pinfunction "CFLY-_3") (pintype "passive"))
    )
    (net (code "55") (name "Net-(DA5-+Vin)") (class "Default")
      (node (ref "C41") (pin "2") (pinfunction "2_2") (pintype "passive"))
      (node (ref "DA5") (pin "1") (pinfunction "+Vin_1") (pintype "passive"))
      (node (ref "L1") (pin "4") (pinfunction "4_4") (pintype "passive"))
    )
    (net (code "56") (name "Net-(DA5--Vin)") (class "Default")
      (node (ref "C41") (pin "1") (pinfunction "1_1") (pintype "passive"))
      (node (ref "DA5") (pin "2") (pinfunction "-Vin_2") (pintype "passive"))
      (node (ref "L1") (pin "1") (pinfunction "1_1") (pintype "passive"))
    )
    (net (code "57") (name "Net-(DA6-C_IN)") (class "Default")
      (node (ref "C46") (pin "2") (pinfunction "2_2") (pintype "passive"))
      (node (ref "DA6") (pin "3") (pinfunction "C_IN_3") (pintype "input"))
      (node (ref "R24") (pin "2") (pinfunction "2_2") (pintype "passive"))
      (node (ref "R26") (pin "2") (pinfunction "2_2") (pintype "passive"))
    )
    (net (code "58") (name "Net-(DA6-OUT)") (class "Default")
      (node (ref "DA6") (pin "2") (pinfunction "OUT_2") (pintype "output"))
      (node (ref "R24") (pin "1") (pinfunction "1_1") (pintype "passive"))
    )
    (net (code "59") (name "Net-(R4-Pad1)") (class "Default")
      (node (ref "R4") (pin "1") (pinfunction "1_1") (pintype "passive"))
      (node (ref "R5") (pin "2") (pinfunction "2_2") (pintype "passive"))
    )
    (net (code "60") (name "Net-(R5-Pad1)") (class "Default")
      (node (ref "R5") (pin "1") (pinfunction "1_1") (pintype "passive"))
      (node (ref "R7") (pin "1") (pinfunction "1_1") (pintype "passive"))
    )
    (net (code "61") (name "Net-(R10-Pad2)") (class "Default")
      (node (ref "R10") (pin "2") (pinfunction "2_2") (pintype "passive"))
      (node (ref "R9") (pin "1") (pinfunction "1_1") (pintype "passive"))
    )
    (net (code "62") (name "Net-(VD5-ANODE)") (class "Default")
      (node (ref "R22") (pin "1") (pinfunction "1_1") (pintype "passive"))
      (node (ref "VD5") (pin "1") (pinfunction "ANODE_1") (pintype "passive"))
    )
    (net (code "63") (name "Net-(VD5-CATHODE)") (class "Default")
      (node (ref "VD5") (pin "2") (pinfunction "CATHODE_2") (pintype "passive"))
      (node (ref "VT1") (pin "3") (pinfunction "C_3") (pintype "passive"))
    )
    (net (code "64") (name "Net-(VD6-ANODE)") (class "Default")
      (node (ref "R23") (pin "1") (pinfunction "1_1") (pintype "passive"))
      (node (ref "VD6") (pin "1") (pinfunction "ANODE_1") (pintype "passive"))
    )
    (net (code "65") (name "Net-(VD6-CATHODE)") (class "Default")
      (node (ref "VD6") (pin "2") (pinfunction "CATHODE_2") (pintype "passive"))
      (node (ref "VT2") (pin "3") (pinfunction "C_3") (pintype "passive"))
    )
    (net (code "66") (name "PRT_1") (class "Default")
      (node (ref "DA3") (pin "6") (pinfunction "C_OUT_6") (pintype "output"))
      (node (ref "R17") (pin "1") (pinfunction "1_1") (pintype "passive"))
      (node (ref "VD1") (pin "2") (pinfunction "ANODE_2") (pintype "passive"))
      (node (ref "VT1") (pin "1") (pinfunction "B_1") (pintype "passive"))
    )
    (net (code "67") (name "PRT_2") (class "Default")
      (node (ref "DA6") (pin "6") (pinfunction "C_OUT_6") (pintype "output"))
      (node (ref "R21") (pin "1") (pinfunction "1_1") (pintype "passive"))
      (node (ref "VD3") (pin "2") (pinfunction "ANODE_2") (pintype "passive"))
      (node (ref "VT2") (pin "1") (pinfunction "B_1") (pintype "passive"))
    )
    (net (code "68") (name "V5_C") (class "Default")
      (node (ref "C14") (pin "2") (pinfunction "2_2") (pintype "passive"))
      (node (ref "C15") (pin "2") (pinfunction "2_2") (pintype "passive"))
      (node (ref "C21") (pin "2") (pinfunction "2_2") (pintype "passive"))
      (node (ref "C30") (pin "2") (pinfunction "2_2") (pintype "passive"))
      (node (ref "C38") (pin "2") (pinfunction "2_2") (pintype "passive"))
      (node (ref "DD1") (pin "1") (pinfunction "VDD1_1") (pintype "power_in"))
      (node (ref "DD2") (pin "1") (pinfunction "VDD1_1") (pintype "power_in"))
      (node (ref "DD2") (pin "7") (pinfunction "VE1_7") (pintype "input"))
      (node (ref "DD3") (pin "1") (pinfunction "VDD1_1") (pintype "power_in"))
      (node (ref "X2") (pin "1B") (pinfunction "1B_1B") (pintype "passive"))
    )
    (net (code "69") (name "V12_C") (class "Default")
      (node (ref "C43") (pin "2") (pinfunction "2_2") (pintype "passive"))
      (node (ref "C44") (pin "2") (pinfunction "2_2") (pintype "passive"))
      (node (ref "L1") (pin "3") (pinfunction "3_3") (pintype "passive"))
      (node (ref "X2") (pin "2A") (pinfunction "2A_2A") (pintype "passive"))
    )
    (net (code "70") (name "gndA") (class "Default")
      (node (ref "C1") (pin "1") (pinfunction "1_1") (pintype "passive"))
      (node (ref "C10") (pin "2") (pinfunction "2_2") (pintype "passive"))
      (node (ref "C11") (pin "1") (pinfunction "1_1") (pintype "passive"))
      (node (ref "C12") (pin "1") (pinfunction "1_1") (pintype "passive"))
      (node (ref "C13") (pin "1") (pinfunction "1_1") (pintype "passive"))
      (node (ref "C18") (pin "1") (pinfunction "1_1") (pintype "passive"))
      (node (ref "C19") (pin "1") (pinfunction "1_1") (pintype "passive"))
      (node (ref "C2") (pin "2") (pinfunction "2_2") (pintype "passive"))
      (node (ref "C20") (pin "1") (pinfunction "1_1") (pintype "passive"))
      (node (ref "C24") (pin "2") (pinfunction "2_2") (pintype "passive"))
      (node (ref "C29") (pin "1") (pinfunction "1_1") (pintype "passive"))
      (node (ref "C31") (pin "1") (pinfunction "1_1") (pintype "passive"))
      (node (ref "C32") (pin "1") (pinfunction "1_1") (pintype "passive"))
      (node (ref "C33") (pin "1") (pinfunction "1_1") (pintype "passive"))
      (node (ref "C34") (pin "1") (pinfunction "1_1") (pintype "passive"))
      (node (ref "C36") (pin "1") (pinfunction "1_1") (pintype "passive"))
      (node (ref "C37") (pin "1") (pinfunction "1_1") (pintype "passive"))
      (node (ref "C39") (pin "1") (pinfunction "1_1") (pintype "passive"))
      (node (ref "C4") (pin "1") (pinfunction "1_1") (pintype "passive"))
      (node (ref "C40") (pin "1") (pinfunction "1_1") (pintype "passive"))
      (node (ref "C42") (pin "1") (pinfunction "1_1") (pintype "passive"))
      (node (ref "C45") (pin "1") (pinfunction "1_1") (pintype "passive"))
      (node (ref "C46") (pin "1") (pinfunction "1_1") (pintype "passive"))
      (node (ref "C5") (pin "2") (pinfunction "2_2") (pintype "passive"))
      (node (ref "C6") (pin "2") (pinfunction "2_2") (pintype "passive"))
      (node (ref "C7") (pin "2") (pinfunction "2_2") (pintype "passive"))
      (node (ref "C8") (pin "2") (pinfunction "2_2") (pintype "passive"))
      (node (ref "C9") (pin "2") (pinfunction "2_2") (pintype "passive"))
      (node (ref "DA1") (pin "11") (pinfunction "AUX_GND_11") (pintype "passive"))
      (node (ref "DA1") (pin "22") (pinfunction "AIN_3GND_22") (pintype "passive"))
      (node (ref "DA1") (pin "23") (pinfunction "AIN_3P_23") (pintype "passive"))
      (node (ref "DA1") (pin "28") (pinfunction "AGND_28") (pintype "passive"))
      (node (ref "DA1") (pin "29") (pinfunction "AGND_29") (pintype "passive"))
      (node (ref "DA1") (pin "3") (pinfunction "DAISY_3") (pintype "power_in"))
      (node (ref "DA1") (pin "31") (pinfunction "AGND_31") (pintype "passive"))
      (node (ref "DA1") (pin "32") (pinfunction "AGND_32") (pintype "passive"))
      (node (ref "DA1") (pin "33") (pinfunction "DGND_33") (pintype "passive"))
      (node (ref "DA1") (pin "4") (pinfunction "~{REFSEL}_4") (pintype "power_in"))
      (node (ref "DA1") (pin "6") (pinfunction "REFGND_6") (pintype "power_in"))
      (node (ref "DA1") (pin "8") (pinfunction "AGND_8") (pintype "passive"))
      (node (ref "DA3") (pin "4") (pinfunction "GND_4") (pintype "power_in"))
      (node (ref "DA3") (pin "7") (pinfunction "V_IN-_7") (pintype "input"))
      (node (ref "DA4") (pin "4") (pinfunction "GND_4") (pintype "power_in"))
      (node (ref "DA5") (pin "5") (pinfunction "-Vout_5") (pintype "passive"))
      (node (ref "DA6") (pin "4") (pinfunction "GND_4") (pintype "power_in"))
      (node (ref "DA6") (pin "8") (pinfunction "V_IN+_8") (pintype "input"))
      (node (ref "DD1") (pin "5") (pinfunction "GND2_5") (pintype "power_in"))
      (node (ref "DD2") (pin "15") (pinfunction "GND2_15") (pintype "power_in"))
      (node (ref "DD2") (pin "9") (pinfunction "GND2_9") (pintype "power_in"))
      (node (ref "DD3") (pin "5") (pinfunction "GND2_5") (pintype "power_in"))
      (node (ref "R10") (pin "1") (pinfunction "1_1") (pintype "passive"))
      (node (ref "R12") (pin "1") (pinfunction "1_1") (pintype "passive"))
      (node (ref "R14") (pin "1") (pinfunction "1_1") (pintype "passive"))
      (node (ref "R15") (pin "1") (pinfunction "1_1") (pintype "passive"))
      (node (ref "R18") (pin "1") (pinfunction "1_1") (pintype "passive"))
      (node (ref "R20") (pin "1") (pinfunction "1_1") (pintype "passive"))
      (node (ref "R25") (pin "1") (pinfunction "1_1") (pintype "passive"))
      (node (ref "R26") (pin "1") (pinfunction "1_1") (pintype "passive"))
      (node (ref "R3") (pin "1") (pinfunction "1_1") (pintype "passive"))
      (node (ref "R7") (pin "2") (pinfunction "2_2") (pintype "passive"))
      (node (ref "VD2") (pin "2") (pinfunction "CATHODE_2") (pintype "passive"))
      (node (ref "VD4") (pin "1") (pinfunction "ANODE_1") (pintype "passive"))
      (node (ref "VT1") (pin "2") (pinfunction "E_2") (pintype "passive"))
      (node (ref "VT2") (pin "2") (pinfunction "E_2") (pintype "passive"))
      (node (ref "X1") (pin "6") (pinfunction "6_6") (pintype "passive"))
    )
    (net (code "71") (name "unconnected-(DA1-NC-Pad12)") (class "Default")
      (node (ref "DA1") (pin "12") (pinfunction "NC_12") (pintype "passive"))
    )
    (net (code "72") (name "unconnected-(DA1-NC-Pad13)") (class "Default")
      (node (ref "DA1") (pin "13") (pinfunction "NC_13") (pintype "passive"))
    )
    (net (code "73") (name "unconnected-(DA1-NC-Pad14)") (class "Default")
      (node (ref "DA1") (pin "14") (pinfunction "NC_14") (pintype "passive"))
    )
    (net (code "74") (name "unconnected-(DA1-NC-Pad15)") (class "Default")
      (node (ref "DA1") (pin "15") (pinfunction "NC_15") (pintype "passive"))
    )
    (net (code "75") (name "unconnected-(DA1-NC-Pad24)") (class "Default")
      (node (ref "DA1") (pin "24") (pinfunction "NC_24") (pintype "passive"))
    )
    (net (code "76") (name "unconnected-(DA1-NC-Pad25)") (class "Default")
      (node (ref "DA1") (pin "25") (pinfunction "NC_25") (pintype "passive"))
    )
    (net (code "77") (name "unconnected-(DA1-NC-Pad26)") (class "Default")
      (node (ref "DA1") (pin "26") (pinfunction "NC_26") (pintype "passive"))
    )
    (net (code "78") (name "unconnected-(DA1-NC-Pad27)") (class "Default")
      (node (ref "DA1") (pin "27") (pinfunction "NC_27") (pintype "passive"))
    )
    (net (code "79") (name "unconnected-(DA5-No_pin-Pad6)") (class "Default")
      (node (ref "DA5") (pin "6") (pinfunction "No_pin_6") (pintype "passive"))
    )
    (net (code "80") (name "unconnected-(RN2-Pad1)") (class "Default")
      (node (ref "RN2") (pin "1") (pinfunction "1_1") (pintype "passive"))
    )
    (net (code "81") (name "unconnected-(RN2-Pad2)") (class "Default")
      (node (ref "RN2") (pin "2") (pinfunction "2_2") (pintype "passive"))
    )
    (net (code "82") (name "unconnected-(RN2-Pad7)") (class "Default")
      (node (ref "RN2") (pin "7") (pinfunction "7_7") (pintype "passive"))
    )
    (net (code "83") (name "unconnected-(RN2-Pad8)") (class "Default")
      (node (ref "RN2") (pin "8") (pinfunction "8_8") (pintype "passive"))
    )
  )
)
